# EtherWiz_ROM.net
KiCad netlist of a schematic drawn in Altium Designer
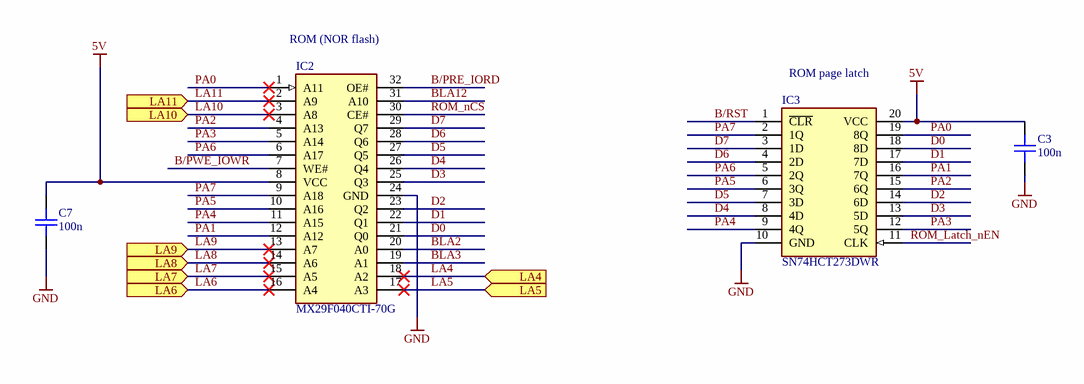
[diagram p0: EtherWiz_ROM.SchDoc]

(export (version "E")
  (design (tool "Eeschema 10.0.6"))
  (components
    (comp (ref "C3")
      (value "100n")
      (footprint "CAPC1608L")
      (description "CAP 100nF, 0603, 50V, X7R, 10%")
      (fields
        (field (name "DISTRIBUTOR1 PART NO") "CL10B104KB8NNNC")
        (field (name "DISTRIBUTOR2 PART NO") "311-1344-2-ND")
      )
      (libsource (lib "MCP1002_RevC") (part "CAP_100n_0603_50V_0"))
    )
    (comp (ref "C7")
      (value "100n")
      (footprint "CAPC1608L")
      (description "CAP 100nF, 0603, 50V, X7R, 10%")
      (fields
        (field (name "DISTRIBUTOR1 PART NO") "CL10B104KB8NNNC")
        (field (name "DISTRIBUTOR2 PART NO") "311-1344-2-ND")
      )
      (libsource (lib "MCP1002_RevC") (part "CAP_100n_0603_50V_0"))
    )
    (comp (ref "IC2")
      (value "MX29F040CTI-70G")
      (footprint "SamacSys:SOP50P2000X120-32N")
      (description "Integrated Circuit")
      (libsource (lib "*") (part "MX29F040CTI-70G"))
    )
    (comp (ref "IC3")
      (value "SN74HCT273DWR")
      (footprint "SamacSys:SOIC127P1030X265-20N")
      (description "Integrated Circuit")
      (fields (field (name "MOUSER PART NUMBER") "595-SN74HCT273DWR"))
      (libsource (lib "*") (part "SN74HCT273DWR"))
    )
  )
  (nets
    (net (code "1") (name "/BLA2") (class "Default")
      (node (ref "IC2") (pin "20") (pinfunction "A0_20") (pintype "passive"))
    )
    (net (code "2") (name "/BLA3") (class "Default")
      (node (ref "IC2") (pin "19") (pinfunction "A1_19") (pintype "passive"))
    )
    (net (code "3") (name "/BLA12") (class "Default")
      (node (ref "IC2") (pin "31") (pinfunction "A10_31") (pintype "passive"))
    )
    (net (code "4") (name "/B{slash}PRE_IORD") (class "Default")
      (node (ref "IC2") (pin "32") (pinfunction "OE#_32") (pintype "passive"))
    )
    (net (code "5") (name "/B{slash}PWE_IOWR") (class "Default")
      (node (ref "IC2") (pin "7") (pinfunction "WE#_7") (pintype "passive"))
    )
    (net (code "6") (name "/B{slash}RST") (class "Default")
      (node (ref "IC3") (pin "1") (pinfunction "~{CLR}_1") (pintype "passive"))
    )
    (net (code "7") (name "/D0") (class "Default")
      (node (ref "IC2") (pin "21") (pinfunction "Q0_21") (pintype "passive"))
      (node (ref "IC3") (pin "18") (pinfunction "8D_18") (pintype "passive"))
    )
    (net (code "8") (name "/D1") (class "Default")
      (node (ref "IC2") (pin "22") (pinfunction "Q1_22") (pintype "passive"))
      (node (ref "IC3") (pin "17") (pinfunction "7D_17") (pintype "passive"))
    )
    (net (code "9") (name "/D2") (class "Default")
      (node (ref "IC2") (pin "23") (pinfunction "Q2_23") (pintype "passive"))
      (node (ref "IC3") (pin "14") (pinfunction "6D_14") (pintype "passive"))
    )
    (net (code "10") (name "/D3") (class "Default")
      (node (ref "IC2") (pin "25") (pinfunction "Q3_25") (pintype "passive"))
      (node (ref "IC3") (pin "13") (pinfunction "5D_13") (pintype "passive"))
    )
    (net (code "11") (name "/D4") (class "Default")
      (node (ref "IC2") (pin "26") (pinfunction "Q4_26") (pintype "passive"))
      (node (ref "IC3") (pin "8") (pinfunction "4D_8") (pintype "passive"))
    )
    (net (code "12") (name "/D5") (class "Default")
      (node (ref "IC2") (pin "27") (pinfunction "Q5_27") (pintype "passive"))
      (node (ref "IC3") (pin "7") (pinfunction "3D_7") (pintype "passive"))
    )
    (net (code "13") (name "/D6") (class "Default")
      (node (ref "IC2") (pin "28") (pinfunction "Q6_28") (pintype "passive"))
      (node (ref "IC3") (pin "4") (pinfunction "2D_4") (pintype "passive"))
    )
    (net (code "14") (name "/D7") (class "Default")
      (node (ref "IC2") (pin "29") (pinfunction "Q7_29") (pintype "passive"))
      (node (ref "IC3") (pin "3") (pinfunction "1D_3") (pintype "passive"))
    )
    (net (code "15") (name "/LA4") (class "Default")
      (node (ref "IC2") (pin "18") (pinfunction "A2_18") (pintype "passive+no_connect"))
    )
    (net (code "16") (name "/LA5") (class "Default")
      (node (ref "IC2") (pin "17") (pinfunction "A3_17") (pintype "passive+no_connect"))
    )
    (net (code "17") (name "/LA6") (class "Default")
      (node (ref "IC2") (pin "16") (pinfunction "A4_16") (pintype "passive+no_connect"))
    )
    (net (code "18") (name "/LA7") (class "Default")
      (node (ref "IC2") (pin "15") (pinfunction "A5_15") (pintype "passive+no_connect"))
    )
    (net (code "19") (name "/LA8") (class "Default")
      (node (ref "IC2") (pin "14") (pinfunction "A6_14") (pintype "passive+no_connect"))
    )
    (net (code "20") (name "/LA9") (class "Default")
      (node (ref "IC2") (pin "13") (pinfunction "A7_13") (pintype "passive+no_connect"))
    )
    (net (code "21") (name "/LA10") (class "Default")
      (node (ref "IC2") (pin "3") (pinfunction "A8_3") (pintype "passive+no_connect"))
    )
    (net (code "22") (name "/LA11") (class "Default")
      (node (ref "IC2") (pin "2") (pinfunction "A9_2") (pintype "passive+no_connect"))
    )
    (net (code "23") (name "/PA0") (class "Default")
      (node (ref "IC2") (pin "1") (pinfunction "A11_1") (pintype "input"))
      (node (ref "IC3") (pin "19") (pinfunction "8Q_19") (pintype "passive"))
    )
    (net (code "24") (name "/PA1") (class "Default")
      (node (ref "IC2") (pin "12") (pinfunction "A12_12") (pintype "passive"))
      (node (ref "IC3") (pin "16") (pinfunction "7Q_16") (pintype "passive"))
    )
    (net (code "25") (name "/PA2") (class "Default")
      (node (ref "IC2") (pin "4") (pinfunction "A13_4") (pintype "passive"))
      (node (ref "IC3") (pin "15") (pinfunction "6Q_15") (pintype "passive"))
    )
    (net (code "26") (name "/PA3") (class "Default")
      (node (ref "IC2") (pin "5") (pinfunction "A14_5") (pintype "passive"))
      (node (ref "IC3") (pin "12") (pinfunction "5Q_12") (pintype "passive"))
    )
    (net (code "27") (name "/PA4") (class "Default")
      (node (ref "IC2") (pin "11") (pinfunction "A15_11") (pintype "passive"))
      (node (ref "IC3") (pin "9") (pinfunction "4Q_9") (pintype "passive"))
    )
    (net (code "28") (name "/PA5") (class "Default")
      (node (ref "IC2") (pin "10") (pinfunction "A16_10") (pintype "passive"))
      (node (ref "IC3") (pin "6") (pinfunction "3Q_6") (pintype "passive"))
    )
    (net (code "29") (name "/PA6") (class "Default")
      (node (ref "IC2") (pin "6") (pinfunction "A17_6") (pintype "passive"))
      (node (ref "IC3") (pin "5") (pinfunction "2Q_5") (pintype "passive"))
    )
    (net (code "30") (name "/PA7") (class "Default")
      (node (ref "IC2") (pin "9") (pinfunction "A18_9") (pintype "passive"))
      (node (ref "IC3") (pin "2") (pinfunction "1Q_2") (pintype "passive"))
    )
    (net (code "31") (name "/ROM_Latch_nEN") (class "Default")
      (node (ref "IC3") (pin "11") (pinfunction "CLK_11") (pintype "input"))
    )
    (net (code "32") (name "/ROM_nCS") (class "Default")
      (node (ref "IC2") (pin "30") (pinfunction "CE#_30") (pintype "passive"))
    )
    (net (code "33") (name "5V") (class "Default")
      (node (ref "C3") (pin "2") (pintype "passive"))
      (node (ref "C7") (pin "2") (pintype "passive"))
      (node (ref "IC2") (pin "8") (pinfunction "VCC_8") (pintype "passive"))
      (node (ref "IC3") (pin "20") (pinfunction "VCC_20") (pintype "power_in"))
    )
    (net (code "34") (name "GND") (class "Default")
      (node (ref "C3") (pin "1") (pintype "passive"))
      (node (ref "C7") (pin "1") (pintype "passive"))
      (node (ref "IC2") (pin "24") (pinfunction "GND_24") (pintype "passive"))
      (node (ref "IC3") (pin "10") (pinfunction "GND_10") (pintype "power_in"))
    )
  )
)
